# 5_-PEAKMETER_LEDS.net
KiCad netlist of a schematic drawn in Altium Designer
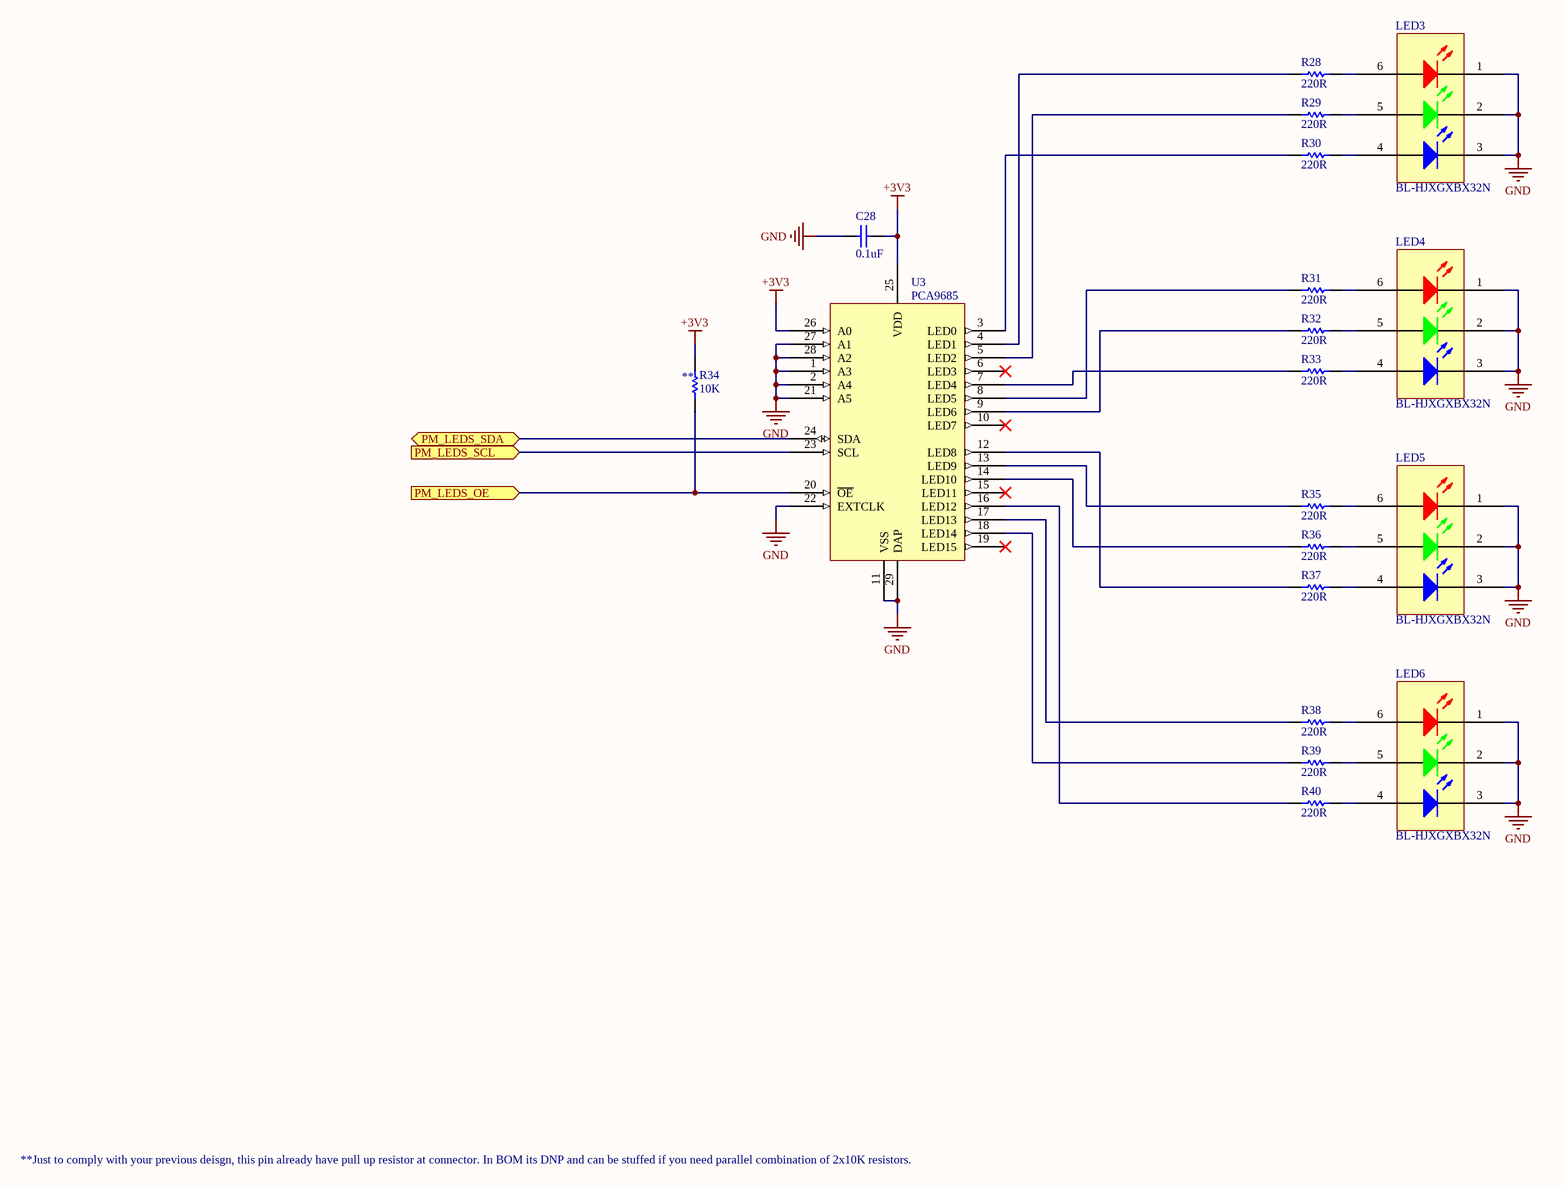
[diagram p0: [5]-PEAKMETER_LEDS.SchDoc]

(export (version "E")
  (design (tool "Eeschema 10.0.6"))
  (components
    (comp (ref "C28")
      (value "0.1uF")
      (footprint "CAPC1608N")
      (description "CAP CER 0.1UF 25V X7R 0603")
      (fields (field (name "TOLERANCE") "10%") (field (name "VOLTAGE") "25V"))
      (libsource (lib "bitsnio") (part "CC0603KRX7R8BB104"))
    )
    (comp (ref "LED3")
      (value "BL-HJXGXBX32N")
      (footprint "BL-HJXGXBX32N")
      (description "LED RGB 6PLCC SMD")
      (libsource (lib "bitsnio") (part "BL-HJXGXBX32N"))
    )
    (comp (ref "LED4")
      (value "BL-HJXGXBX32N")
      (footprint "BL-HJXGXBX32N")
      (description "LED RGB 6PLCC SMD")
      (libsource (lib "bitsnio") (part "BL-HJXGXBX32N"))
    )
    (comp (ref "LED5")
      (value "BL-HJXGXBX32N")
      (footprint "BL-HJXGXBX32N")
      (description "LED RGB 6PLCC SMD")
      (libsource (lib "bitsnio") (part "BL-HJXGXBX32N"))
    )
    (comp (ref "LED6")
      (value "BL-HJXGXBX32N")
      (footprint "BL-HJXGXBX32N")
      (description "LED RGB 6PLCC SMD")
      (libsource (lib "bitsnio") (part "BL-HJXGXBX32N"))
    )
    (comp (ref "R28")
      (value "220R")
      (footprint "RESC1608N")
      (description "RES SMD 220 OHM 5% 1/10W 0603")
      (fields (field (name "TOLERANCE") "5%"))
      (libsource (lib "bitsnio") (part "CRCW0603220RJNEA"))
    )
    (comp (ref "R29")
      (value "220R")
      (footprint "RESC1608N")
      (description "RES SMD 220 OHM 5% 1/10W 0603")
      (fields (field (name "TOLERANCE") "5%"))
      (libsource (lib "bitsnio") (part "CRCW0603220RJNEA"))
    )
    (comp (ref "R30")
      (value "220R")
      (footprint "RESC1608N")
      (description "RES SMD 220 OHM 5% 1/10W 0603")
      (fields (field (name "TOLERANCE") "5%"))
      (libsource (lib "bitsnio") (part "CRCW0603220RJNEA"))
    )
    (comp (ref "R31")
      (value "220R")
      (footprint "RESC1608N")
      (description "RES SMD 220 OHM 5% 1/10W 0603")
      (fields (field (name "TOLERANCE") "5%"))
      (libsource (lib "bitsnio") (part "CRCW0603220RJNEA"))
    )
    (comp (ref "R32")
      (value "220R")
      (footprint "RESC1608N")
      (description "RES SMD 220 OHM 5% 1/10W 0603")
      (fields (field (name "TOLERANCE") "5%"))
      (libsource (lib "bitsnio") (part "CRCW0603220RJNEA"))
    )
    (comp (ref "R33")
      (value "220R")
      (footprint "RESC1608N")
      (description "RES SMD 220 OHM 5% 1/10W 0603")
      (fields (field (name "TOLERANCE") "5%"))
      (libsource (lib "bitsnio") (part "CRCW0603220RJNEA"))
    )
    (comp (ref "R34")
      (value "10K")
      (footprint "RESC1608N")
      (description "RES SMD 10K OHM 5% 1/10W 0603")
      (fields (field (name "TOLERANCE") "5%"))
      (libsource (lib "bitsnio") (part "AC0603JR-0710KL"))
    )
    (comp (ref "R35")
      (value "220R")
      (footprint "RESC1608N")
      (description "RES SMD 220 OHM 5% 1/10W 0603")
      (fields (field (name "TOLERANCE") "5%"))
      (libsource (lib "bitsnio") (part "CRCW0603220RJNEA"))
    )
    (comp (ref "R36")
      (value "220R")
      (footprint "RESC1608N")
      (description "RES SMD 220 OHM 5% 1/10W 0603")
      (fields (field (name "TOLERANCE") "5%"))
      (libsource (lib "bitsnio") (part "CRCW0603220RJNEA"))
    )
    (comp (ref "R37")
      (value "220R")
      (footprint "RESC1608N")
      (description "RES SMD 220 OHM 5% 1/10W 0603")
      (fields (field (name "TOLERANCE") "5%"))
      (libsource (lib "bitsnio") (part "CRCW0603220RJNEA"))
    )
    (comp (ref "R38")
      (value "220R")
      (footprint "RESC1608N")
      (description "RES SMD 220 OHM 5% 1/10W 0603")
      (fields (field (name "TOLERANCE") "5%"))
      (libsource (lib "bitsnio") (part "CRCW0603220RJNEA"))
    )
    (comp (ref "R39")
      (value "220R")
      (footprint "RESC1608N")
      (description "RES SMD 220 OHM 5% 1/10W 0603")
      (fields (field (name "TOLERANCE") "5%"))
      (libsource (lib "bitsnio") (part "CRCW0603220RJNEA"))
    )
    (comp (ref "R40")
      (value "220R")
      (footprint "RESC1608N")
      (description "RES SMD 220 OHM 5% 1/10W 0603")
      (fields (field (name "TOLERANCE") "5%"))
      (libsource (lib "bitsnio") (part "CRCW0603220RJNEA"))
    )
    (comp (ref "U3")
      (value "PCA9685")
      (footprint "SOT788-1")
      (description "IC LED DRVR LIN DIM 25MA 28HVQFN")
      (libsource (lib "bitsnio") (part "IC_PCA9685BS,118"))
    )
  )
  (nets
    (net (code "1") (name "+3V3") (class "Default")
      (node (ref "C28") (pin "1") (pinfunction "1_1") (pintype "passive"))
      (node (ref "R34") (pin "1") (pinfunction "1_1") (pintype "passive"))
      (node (ref "U3") (pin "25") (pinfunction "VDD_25") (pintype "passive"))
      (node (ref "U3") (pin "26") (pinfunction "A0_26") (pintype "input"))
    )
    (net (code "2") (name "/PM_LEDS_OE") (class "Default")
      (node (ref "R34") (pin "2") (pinfunction "2_2") (pintype "passive"))
      (node (ref "U3") (pin "20") (pinfunction "~{OE}_20") (pintype "input"))
    )
    (net (code "3") (name "/PM_LEDS_SCL") (class "Default")
      (node (ref "U3") (pin "23") (pinfunction "SCL_23") (pintype "input"))
    )
    (net (code "4") (name "/PM_LEDS_SDA") (class "Default")
      (node (ref "U3") (pin "24") (pinfunction "SDA_24") (pintype "bidirectional"))
    )
    (net (code "5") (name "GND") (class "Default")
      (node (ref "C28") (pin "2") (pinfunction "2_2") (pintype "passive"))
      (node (ref "LED3") (pin "1") (pinfunction "1_1") (pintype "passive"))
      (node (ref "LED3") (pin "2") (pinfunction "2_2") (pintype "passive"))
      (node (ref "LED3") (pin "3") (pinfunction "3_3") (pintype "passive"))
      (node (ref "LED4") (pin "1") (pinfunction "1_1") (pintype "passive"))
      (node (ref "LED4") (pin "2") (pinfunction "2_2") (pintype "passive"))
      (node (ref "LED4") (pin "3") (pinfunction "3_3") (pintype "passive"))
      (node (ref "LED5") (pin "1") (pinfunction "1_1") (pintype "passive"))
      (node (ref "LED5") (pin "2") (pinfunction "2_2") (pintype "passive"))
      (node (ref "LED5") (pin "3") (pinfunction "3_3") (pintype "passive"))
      (node (ref "LED6") (pin "1") (pinfunction "1_1") (pintype "passive"))
      (node (ref "LED6") (pin "2") (pinfunction "2_2") (pintype "passive"))
      (node (ref "LED6") (pin "3") (pinfunction "3_3") (pintype "passive"))
      (node (ref "U3") (pin "1") (pinfunction "A3_1") (pintype "input"))
      (node (ref "U3") (pin "11") (pinfunction "VSS_11") (pintype "passive"))
      (node (ref "U3") (pin "2") (pinfunction "A4_2") (pintype "input"))
      (node (ref "U3") (pin "21") (pinfunction "A5_21") (pintype "input"))
      (node (ref "U3") (pin "22") (pinfunction "EXTCLK_22") (pintype "input"))
      (node (ref "U3") (pin "27") (pinfunction "A1_27") (pintype "input"))
      (node (ref "U3") (pin "28") (pinfunction "A2_28") (pintype "input"))
      (node (ref "U3") (pin "29") (pinfunction "DAP_29") (pintype "passive"))
    )
    (net (code "6") (name "Net-(LED3-Pad4)") (class "Default")
      (node (ref "LED3") (pin "4") (pinfunction "4_4") (pintype "passive"))
      (node (ref "R30") (pin "2") (pinfunction "2_2") (pintype "passive"))
    )
    (net (code "7") (name "Net-(LED3-Pad5)") (class "Default")
      (node (ref "LED3") (pin "5") (pinfunction "5_5") (pintype "passive"))
      (node (ref "R29") (pin "2") (pinfunction "2_2") (pintype "passive"))
    )
    (net (code "8") (name "Net-(LED3-Pad6)") (class "Default")
      (node (ref "LED3") (pin "6") (pinfunction "6_6") (pintype "passive"))
      (node (ref "R28") (pin "2") (pinfunction "2_2") (pintype "passive"))
    )
    (net (code "9") (name "Net-(LED4-Pad4)") (class "Default")
      (node (ref "LED4") (pin "4") (pinfunction "4_4") (pintype "passive"))
      (node (ref "R33") (pin "2") (pinfunction "2_2") (pintype "passive"))
    )
    (net (code "10") (name "Net-(LED4-Pad5)") (class "Default")
      (node (ref "LED4") (pin "5") (pinfunction "5_5") (pintype "passive"))
      (node (ref "R32") (pin "2") (pinfunction "2_2") (pintype "passive"))
    )
    (net (code "11") (name "Net-(LED4-Pad6)") (class "Default")
      (node (ref "LED4") (pin "6") (pinfunction "6_6") (pintype "passive"))
      (node (ref "R31") (pin "2") (pinfunction "2_2") (pintype "passive"))
    )
    (net (code "12") (name "Net-(LED5-Pad4)") (class "Default")
      (node (ref "LED5") (pin "4") (pinfunction "4_4") (pintype "passive"))
      (node (ref "R37") (pin "2") (pinfunction "2_2") (pintype "passive"))
    )
    (net (code "13") (name "Net-(LED5-Pad5)") (class "Default")
      (node (ref "LED5") (pin "5") (pinfunction "5_5") (pintype "passive"))
      (node (ref "R36") (pin "2") (pinfunction "2_2") (pintype "passive"))
    )
    (net (code "14") (name "Net-(LED5-Pad6)") (class "Default")
      (node (ref "LED5") (pin "6") (pinfunction "6_6") (pintype "passive"))
      (node (ref "R35") (pin "2") (pinfunction "2_2") (pintype "passive"))
    )
    (net (code "15") (name "Net-(LED6-Pad4)") (class "Default")
      (node (ref "LED6") (pin "4") (pinfunction "4_4") (pintype "passive"))
      (node (ref "R40") (pin "2") (pinfunction "2_2") (pintype "passive"))
    )
    (net (code "16") (name "Net-(LED6-Pad5)") (class "Default")
      (node (ref "LED6") (pin "5") (pinfunction "5_5") (pintype "passive"))
      (node (ref "R39") (pin "2") (pinfunction "2_2") (pintype "passive"))
    )
    (net (code "17") (name "Net-(LED6-Pad6)") (class "Default")
      (node (ref "LED6") (pin "6") (pinfunction "6_6") (pintype "passive"))
      (node (ref "R38") (pin "2") (pinfunction "2_2") (pintype "passive"))
    )
    (net (code "18") (name "Net-(U3-LED0)") (class "Default")
      (node (ref "R30") (pin "1") (pinfunction "1_1") (pintype "passive"))
      (node (ref "U3") (pin "3") (pinfunction "LED0_3") (pintype "output"))
    )
    (net (code "19") (name "Net-(U3-LED1)") (class "Default")
      (node (ref "R28") (pin "1") (pinfunction "1_1") (pintype "passive"))
      (node (ref "U3") (pin "4") (pinfunction "LED1_4") (pintype "output"))
    )
    (net (code "20") (name "Net-(U3-LED2)") (class "Default")
      (node (ref "R29") (pin "1") (pinfunction "1_1") (pintype "passive"))
      (node (ref "U3") (pin "5") (pinfunction "LED2_5") (pintype "output"))
    )
    (net (code "21") (name "Net-(U3-LED4)") (class "Default")
      (node (ref "R33") (pin "1") (pinfunction "1_1") (pintype "passive"))
      (node (ref "U3") (pin "7") (pinfunction "LED4_7") (pintype "output"))
    )
    (net (code "22") (name "Net-(U3-LED5)") (class "Default")
      (node (ref "R31") (pin "1") (pinfunction "1_1") (pintype "passive"))
      (node (ref "U3") (pin "8") (pinfunction "LED5_8") (pintype "output"))
    )
    (net (code "23") (name "Net-(U3-LED6)") (class "Default")
      (node (ref "R32") (pin "1") (pinfunction "1_1") (pintype "passive"))
      (node (ref "U3") (pin "9") (pinfunction "LED6_9") (pintype "output"))
    )
    (net (code "24") (name "Net-(U3-LED8)") (class "Default")
      (node (ref "R37") (pin "1") (pinfunction "1_1") (pintype "passive"))
      (node (ref "U3") (pin "12") (pinfunction "LED8_12") (pintype "output"))
    )
    (net (code "25") (name "Net-(U3-LED9)") (class "Default")
      (node (ref "R35") (pin "1") (pinfunction "1_1") (pintype "passive"))
      (node (ref "U3") (pin "13") (pinfunction "LED9_13") (pintype "output"))
    )
    (net (code "26") (name "Net-(U3-LED10)") (class "Default")
      (node (ref "R36") (pin "1") (pinfunction "1_1") (pintype "passive"))
      (node (ref "U3") (pin "14") (pinfunction "LED10_14") (pintype "output"))
    )
    (net (code "27") (name "Net-(U3-LED12)") (class "Default")
      (node (ref "R40") (pin "1") (pinfunction "1_1") (pintype "passive"))
      (node (ref "U3") (pin "16") (pinfunction "LED12_16") (pintype "output"))
    )
    (net (code "28") (name "Net-(U3-LED13)") (class "Default")
      (node (ref "R38") (pin "1") (pinfunction "1_1") (pintype "passive"))
      (node (ref "U3") (pin "17") (pinfunction "LED13_17") (pintype "output"))
    )
    (net (code "29") (name "Net-(U3-LED14)") (class "Default")
      (node (ref "R39") (pin "1") (pinfunction "1_1") (pintype "passive"))
      (node (ref "U3") (pin "18") (pinfunction "LED14_18") (pintype "output"))
    )
    (net (code "30") (name "unconnected-(U3-LED3-Pad6)") (class "Default")
      (node (ref "U3") (pin "6") (pinfunction "LED3_6") (pintype "output+no_connect"))
    )
    (net (code "31") (name "unconnected-(U3-LED7-Pad10)") (class "Default")
      (node (ref "U3") (pin "10") (pinfunction "LED7_10") (pintype "output+no_connect"))
    )
    (net (code "32") (name "unconnected-(U3-LED11-Pad15)") (class "Default")
      (node (ref "U3") (pin "15") (pinfunction "LED11_15") (pintype "output+no_connect"))
    )
    (net (code "33") (name "unconnected-(U3-LED15-Pad19)") (class "Default")
      (node (ref "U3") (pin "19") (pinfunction "LED15_19") (pintype "output+no_connect"))
    )
  )
)
